# TSOC_WaterSensor.net
KiCad netlist of a schematic drawn in EAGLE
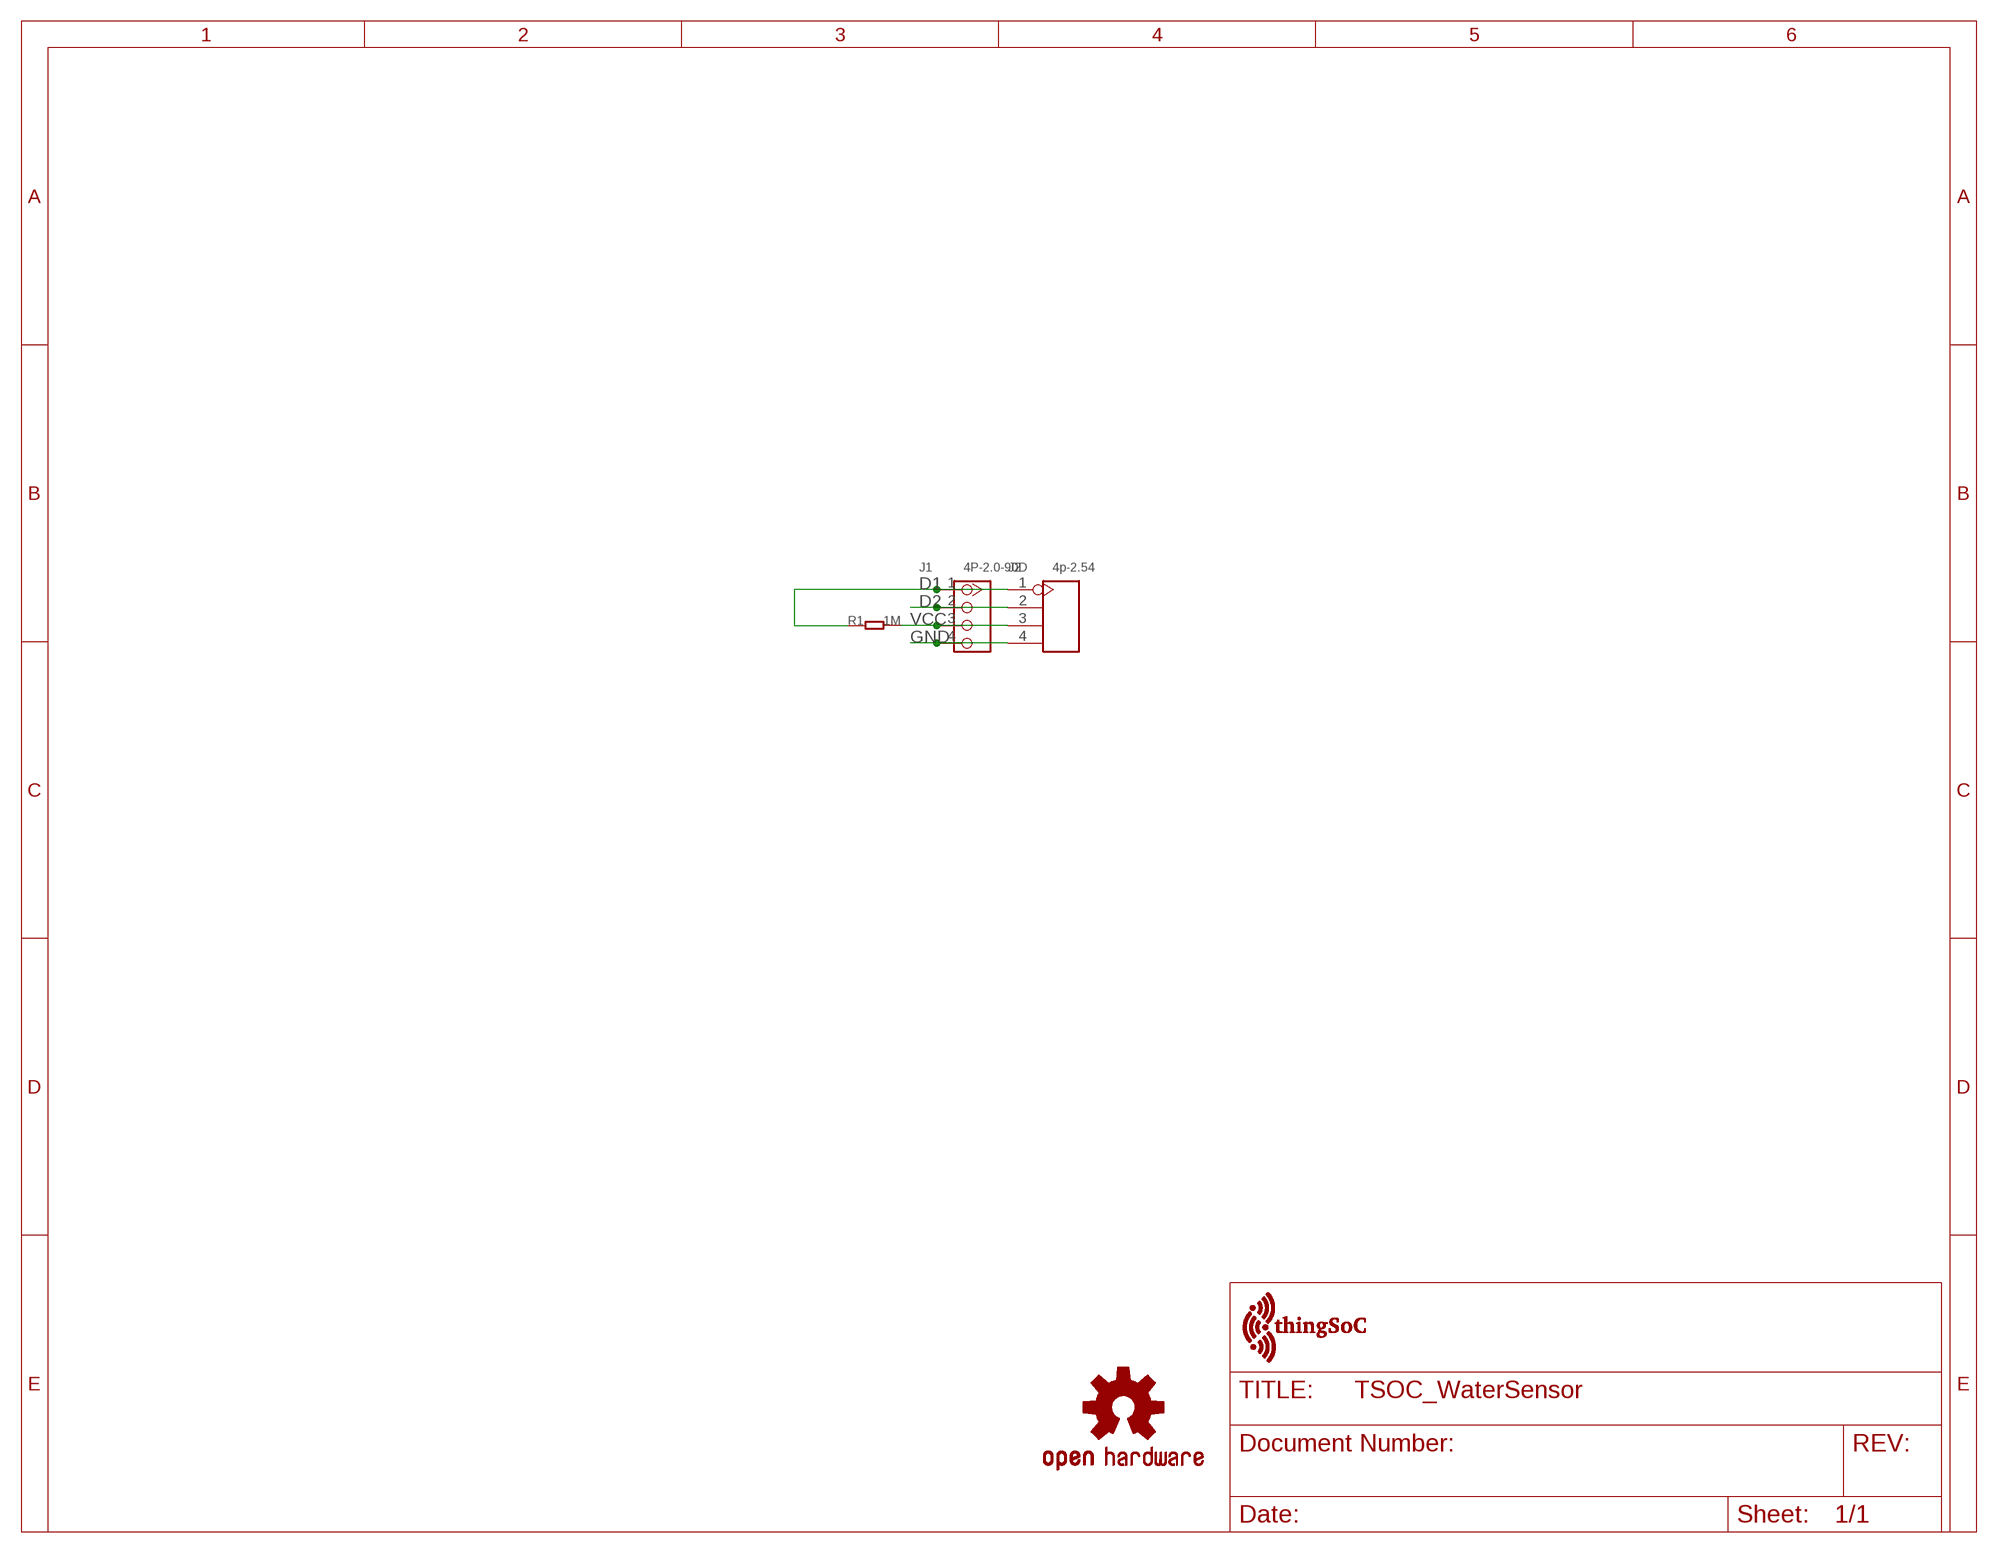
[diagram p0: schematic, sheet 1]

(export (version "E")
  (design (tool "Eeschema 10.0.6"))
  (components
    (comp (ref "J1")
      (value "4P-2.0-90D")
      (footprint "eagle-import:HW4-2.0-90D")
      (libsource (lib "eagle-import") (part "GROVE-CONNECTOR-DIP-90D(4P-2.0)"))
    )
    (comp (ref "J2")
      (value "4p-2.54")
      (footprint "eagle-import:H4-2.54")
      (fields (field (name "MPN") "P125-1104A0BS116A1"))
      (libsource (lib "eagle-import") (part "DIP-BLACK-MALE-HEADER-VERT(4P-2.54)"))
    )
    (comp (ref "R1")
      (value "1M")
      (footprint "eagle-import:0603")
      (libsource (lib "eagle-import") (part "R0603"))
    )
    (comp (ref "U$1")
      (value "OSHW_LOGO_SYMM")
      (footprint "eagle-import:OSHW_LOGO_MED_SYM")
      (libsource (lib "eagle-import") (part "OSHW_LOGO_SYMM"))
    )
    (comp (ref "U$2")
      (value "TSOC-LOGO-LRG")
      (footprint "eagle-import:TSOC-LOGO-LRG")
      (libsource (lib "eagle-import") (part "TSOC-LOGO-LRG"))
    )
  )
  (nets
    (net (code "1") (name "/D1") (class "Default")
      (node (ref "J1") (pin "1") (pinfunction "1_1") (pintype "bidirectional"))
      (node (ref "J2") (pin "1") (pinfunction "P$1_1") (pintype "bidirectional"))
      (node (ref "R1") (pin "1") (pinfunction "1_1") (pintype "bidirectional"))
    )
    (net (code "2") (name "/D2") (class "Default")
      (node (ref "J1") (pin "2") (pinfunction "2_2") (pintype "bidirectional"))
      (node (ref "J2") (pin "2") (pinfunction "P$2_2") (pintype "bidirectional"))
    )
    (net (code "3") (name "/GND") (class "Default")
      (node (ref "J1") (pin "4") (pinfunction "4_4") (pintype "bidirectional"))
      (node (ref "J2") (pin "4") (pinfunction "P$4_4") (pintype "bidirectional"))
    )
    (net (code "4") (name "/VCC") (class "Default")
      (node (ref "J1") (pin "3") (pinfunction "3_3") (pintype "bidirectional"))
      (node (ref "J2") (pin "3") (pinfunction "P$3_3") (pintype "bidirectional"))
      (node (ref "R1") (pin "2") (pinfunction "2_2") (pintype "bidirectional"))
    )
  )
)
